# connectors.net
KiCad netlist of a schematic drawn in Altium Designer
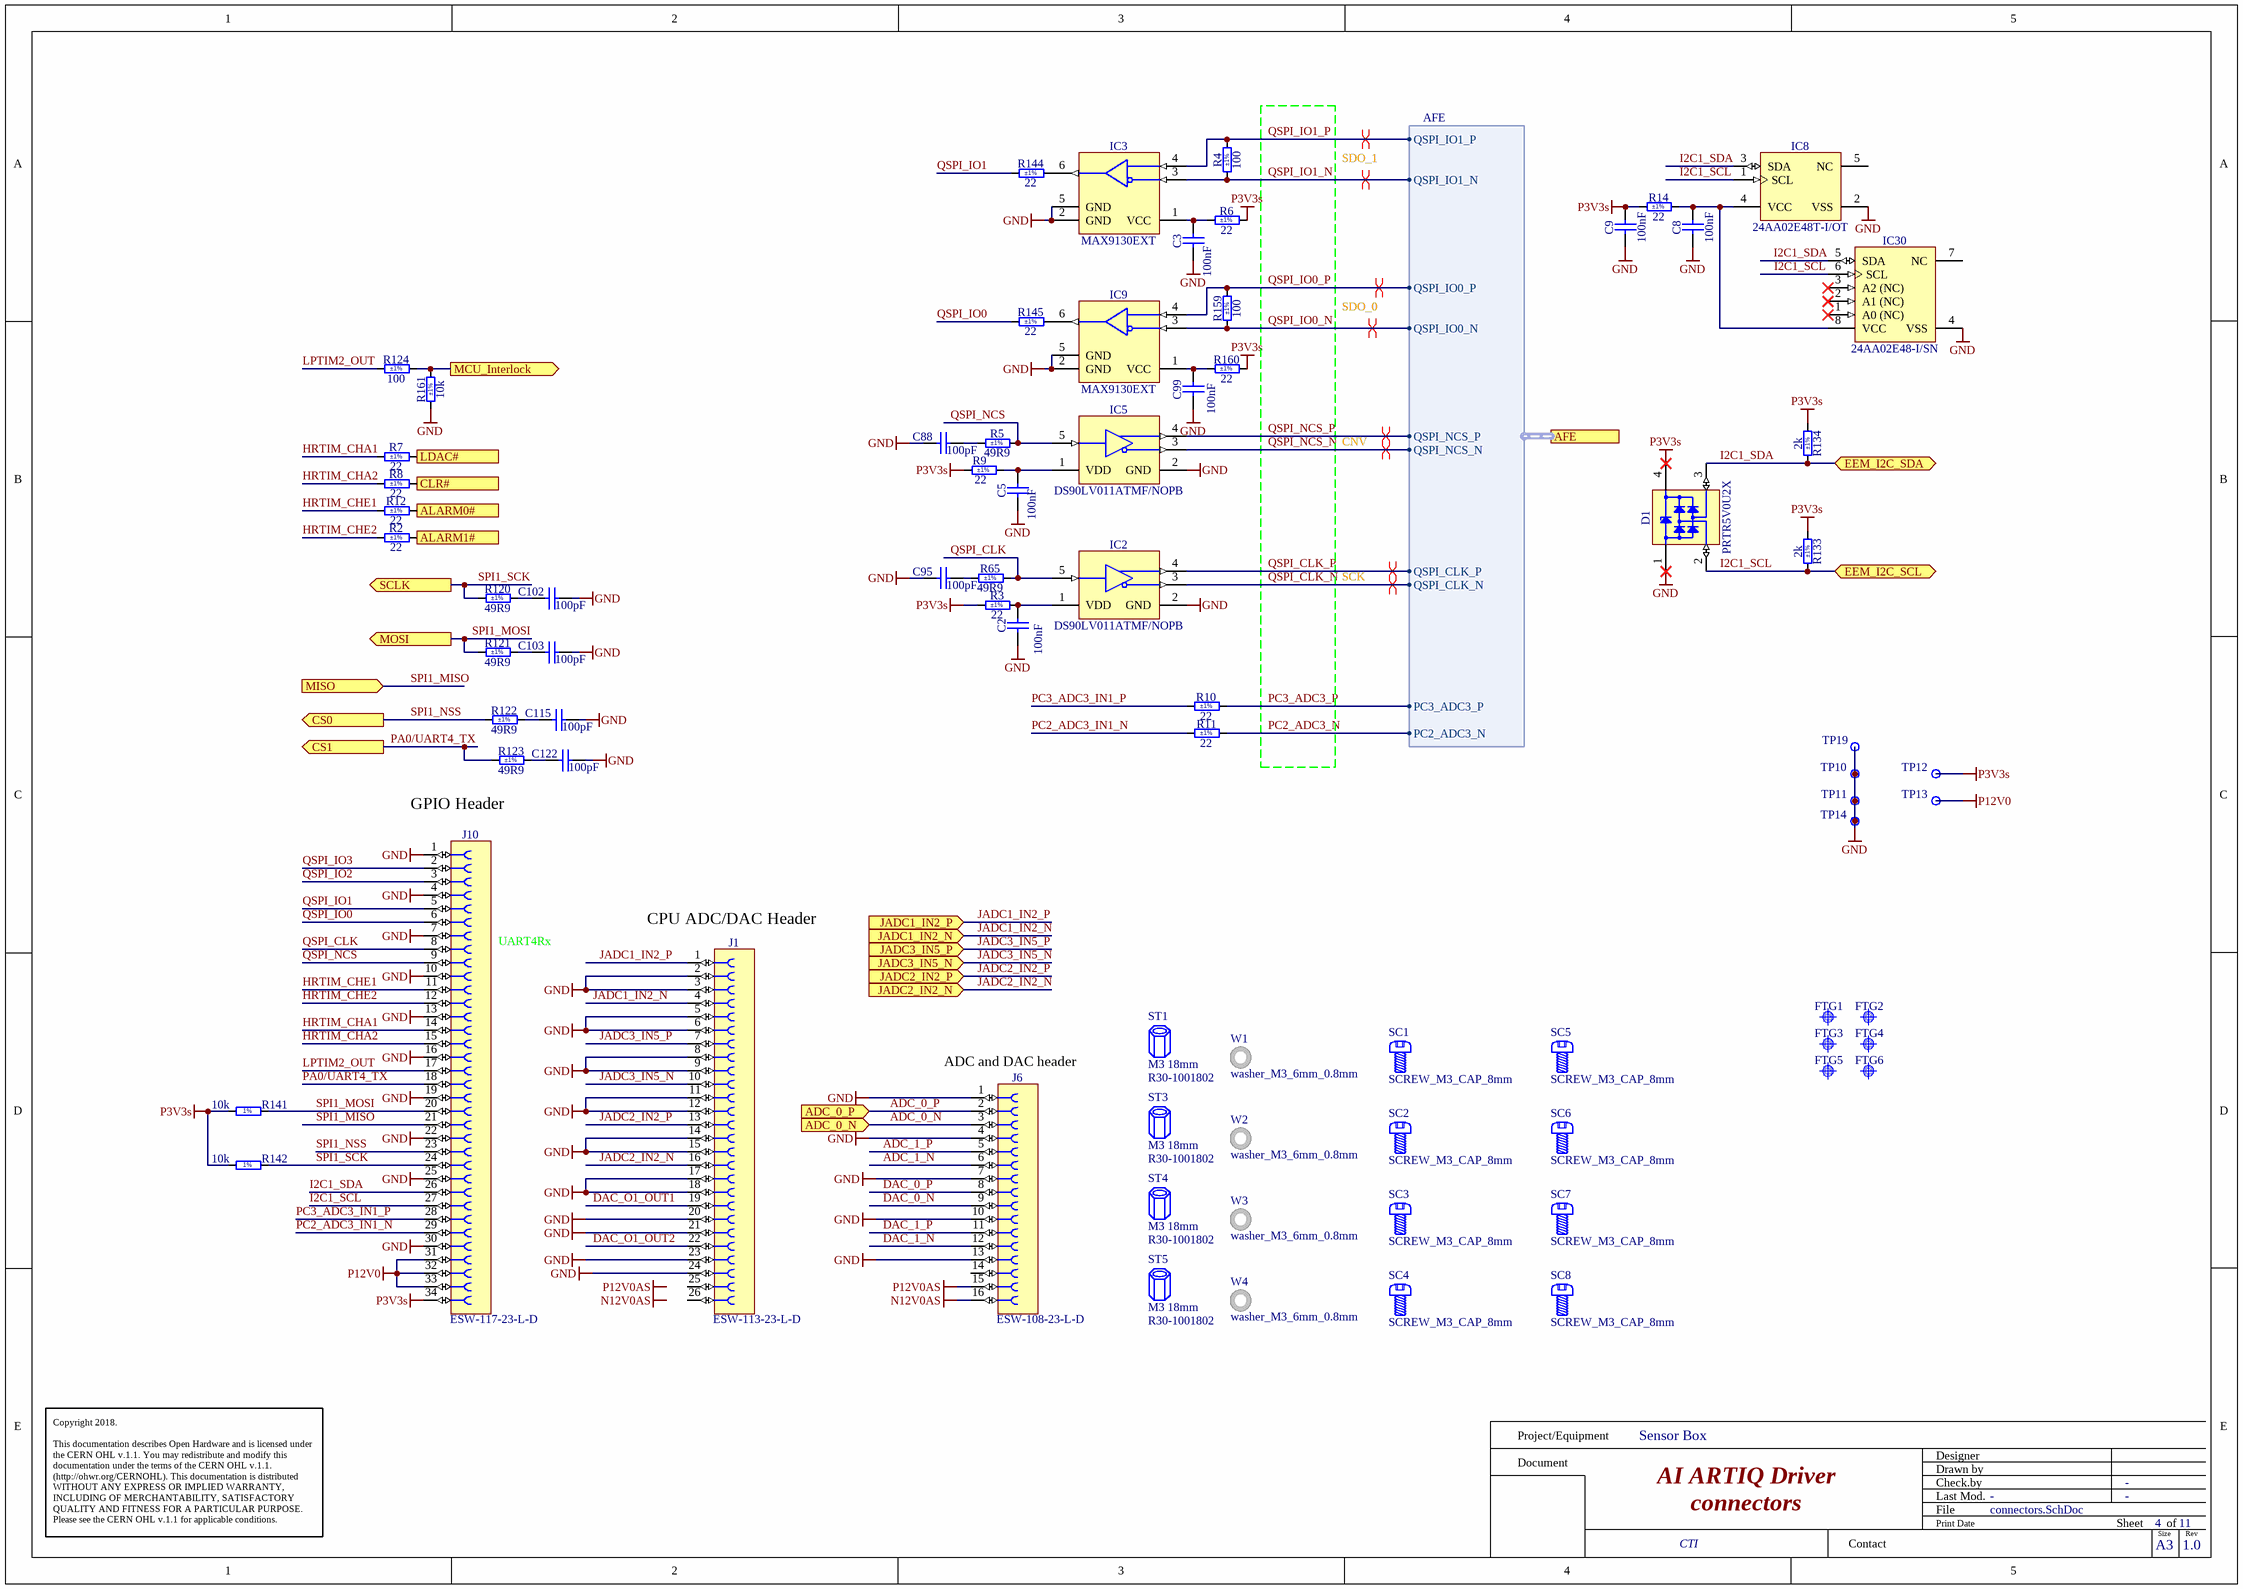
[diagram p0: connectors.SchDoc]

(export (version "E")
  (design (tool "Eeschema 10.0.6"))
  (components
    (comp (ref "C2")
      (value "100nF")
      (footprint "CAPC2012X135N")
      (description "Non-polarised capacitor")
      (fields
        (field (name "PART NUMBER") "CC0805_100NF_50V_10%_X7R")
        (field (name "VOLTAGE") "50V")
        (field (name "AUTHOR") "CERN DEM JLC")
      )
      (libsource (lib "Capacitors") (part "Capacitor - non polarized"))
    )
    (comp (ref "C3")
      (value "100nF")
      (footprint "CAPC2012X135N")
      (description "Non-polarised capacitor")
      (fields
        (field (name "PART NUMBER") "CC0805_100NF_50V_10%_X7R")
        (field (name "VOLTAGE") "50V")
        (field (name "AUTHOR") "CERN DEM JLC")
      )
      (libsource (lib "Capacitors") (part "Capacitor - non polarized"))
    )
    (comp (ref "C5")
      (value "100nF")
      (footprint "CAPC2012X135N")
      (description "Non-polarised capacitor")
      (fields
        (field (name "PART NUMBER") "CC0805_100NF_50V_10%_X7R")
        (field (name "VOLTAGE") "50V")
        (field (name "AUTHOR") "CERN DEM JLC")
      )
      (libsource (lib "Capacitors") (part "Capacitor - non polarized"))
    )
    (comp (ref "C8")
      (value "100nF")
      (footprint "CAPC2012X135N")
      (description "Non-polarised capacitor")
      (fields
        (field (name "PART NUMBER") "CC0805_100NF_50V_10%_X7R")
        (field (name "VOLTAGE") "50V")
        (field (name "AUTHOR") "CERN DEM JLC")
      )
      (libsource (lib "Capacitors") (part "Capacitor - non polarized"))
    )
    (comp (ref "C9")
      (value "100nF")
      (footprint "CAPC2012X135N")
      (description "Non-polarised capacitor")
      (fields
        (field (name "PART NUMBER") "CC0805_100NF_50V_10%_X7R")
        (field (name "VOLTAGE") "50V")
        (field (name "AUTHOR") "CERN DEM JLC")
      )
      (libsource (lib "Capacitors") (part "Capacitor - non polarized"))
    )
    (comp (ref "C88")
      (value "100pF")
      (footprint "CAPC1005X55N")
      (description "Non-polarised capacitor")
      (fields
        (field (name "PART NUMBER") "CC0402_100PF_50V_5%_C0G")
        (field (name "VOLTAGE") "50V")
        (field (name "AUTHOR") "CERN DEM JLC")
      )
      (libsource (lib "Capacitors") (part "Capacitor - non polarized"))
    )
    (comp (ref "C95")
      (value "100pF")
      (footprint "CAPC1005X55N")
      (description "Non-polarised capacitor")
      (fields
        (field (name "PART NUMBER") "CC0402_100PF_50V_5%_C0G")
        (field (name "VOLTAGE") "50V")
        (field (name "AUTHOR") "CERN DEM JLC")
      )
      (libsource (lib "Capacitors") (part "Capacitor - non polarized"))
    )
    (comp (ref "C99")
      (value "100nF")
      (footprint "CAPC2012X135N")
      (description "Non-polarised capacitor")
      (fields
        (field (name "PART NUMBER") "CC0805_100NF_50V_10%_X7R")
        (field (name "VOLTAGE") "50V")
        (field (name "AUTHOR") "CERN DEM JLC")
      )
      (libsource (lib "Capacitors") (part "Capacitor - non polarized"))
    )
    (comp (ref "C102")
      (value "100pF")
      (footprint "CAPC1005X55N")
      (description "Non-polarised capacitor")
      (fields
        (field (name "PART NUMBER") "CC0402_100PF_50V_5%_C0G")
        (field (name "VOLTAGE") "50V")
        (field (name "AUTHOR") "CERN DEM JLC")
      )
      (libsource (lib "Capacitors") (part "Capacitor - non polarized"))
    )
    (comp (ref "C103")
      (value "100pF")
      (footprint "CAPC1005X55N")
      (description "Non-polarised capacitor")
      (fields
        (field (name "PART NUMBER") "CC0402_100PF_50V_5%_C0G")
        (field (name "VOLTAGE") "50V")
        (field (name "AUTHOR") "CERN DEM JLC")
      )
      (libsource (lib "Capacitors") (part "Capacitor - non polarized"))
    )
    (comp (ref "C115")
      (value "100pF")
      (footprint "CAPC1005X55N")
      (description "Non-polarised capacitor")
      (fields
        (field (name "PART NUMBER") "CC0402_100PF_50V_5%_C0G")
        (field (name "VOLTAGE") "50V")
        (field (name "AUTHOR") "CERN DEM JLC")
      )
      (libsource (lib "Capacitors") (part "Capacitor - non polarized"))
    )
    (comp (ref "C122")
      (value "100pF")
      (footprint "CAPC1005X55N")
      (description "Non-polarised capacitor")
      (fields
        (field (name "PART NUMBER") "CC0402_100PF_50V_5%_C0G")
        (field (name "VOLTAGE") "50V")
        (field (name "AUTHOR") "CERN DEM JLC")
      )
      (libsource (lib "Capacitors") (part "Capacitor - non polarized"))
    )
    (comp (ref "D1")
      (value "PRTR5V0U2X")
      (footprint "SOT190P230X110-4N")
      (description "Ultra Low Capacitance Double Rail-to-Rail ESD Protection Diode")
      (fields
        (field (name "VOLTAGE") "5.5V")
        (field (name "MANUFACTURER") "NXP SEMICONDUCTORS")
        (field (name "AUTHOR") "CERN DEM JLC")
      )
      (libsource (lib "ICs And Semiconductors") (part "PRTR5V0U2X"))
    )
    (comp (ref "FTG1")
      (value "Use only in PCB")
      (footprint "FIDUCIAL_TOP_C100-200")
      (description "Fiducial Target")
      (fields (field (name "PART NUMBER") "FIDUCIAL_TARGET_C100-200") (field (name "AUTHOR") "CERN DEM JLC"))
      (libsource (lib "Eletro-mechanical") (part "Fiducial Target"))
    )
    (comp (ref "FTG2")
      (value "Use only in PCB")
      (footprint "FIDUCIAL_TOP_C100-200")
      (description "Fiducial Target")
      (fields (field (name "PART NUMBER") "FIDUCIAL_TARGET_C100-200") (field (name "AUTHOR") "CERN DEM JLC"))
      (libsource (lib "Eletro-mechanical") (part "Fiducial Target"))
    )
    (comp (ref "FTG3")
      (value "Use only in PCB")
      (footprint "FIDUCIAL_TOP_C100-200")
      (description "Fiducial Target")
      (fields (field (name "PART NUMBER") "FIDUCIAL_TARGET_C100-200") (field (name "AUTHOR") "CERN DEM JLC"))
      (libsource (lib "Eletro-mechanical") (part "Fiducial Target"))
    )
    (comp (ref "FTG4")
      (value "Use only in PCB")
      (footprint "FIDUCIAL_TOP_C100-200")
      (description "Fiducial Target")
      (fields (field (name "PART NUMBER") "FIDUCIAL_TARGET_C100-200") (field (name "AUTHOR") "CERN DEM JLC"))
      (libsource (lib "Eletro-mechanical") (part "Fiducial Target"))
    )
    (comp (ref "FTG5")
      (value "Use only in PCB")
      (footprint "FIDUCIAL_TOP_C100-200")
      (description "Fiducial Target")
      (fields (field (name "PART NUMBER") "FIDUCIAL_TARGET_C100-200") (field (name "AUTHOR") "CERN DEM JLC"))
      (libsource (lib "Eletro-mechanical") (part "Fiducial Target"))
    )
    (comp (ref "FTG6")
      (value "Use only in PCB")
      (footprint "FIDUCIAL_TOP_C100-200")
      (description "Fiducial Target")
      (fields (field (name "PART NUMBER") "FIDUCIAL_TARGET_C100-200") (field (name "AUTHOR") "CERN DEM JLC"))
      (libsource (lib "Eletro-mechanical") (part "Fiducial Target"))
    )
    (comp (ref "IC2")
      (value "DS90LV011ATMF/NOPB")
      (footprint "SOT95P284X122-5N")
      (description "3V LVDS Single High Speed Differential Driver")
      (fields
        (field (name "MANUFACTURER") "NATIONAL SEMICONDUCTOR")
        (field (name "MANUFACTURER PART NUMBER") "DS90LV011ATMF")
        (field (name "AUTHOR") "CERN DEM JLC")
      )
      (libsource (lib "ICs And Semiconductors") (part "DS90LV011A"))
    )
    (comp (ref "IC3")
      (value "MAX9130EXT")
      (footprint "SOT65P210X110-6N")
      (description "Single 500Mbps LVDS Line Receiver")
      (fields (field (name "MANUFACTURER") "MAXIM") (field (name "AUTHOR") "CERN DEM HF"))
      (libsource (lib "ICs And Semiconductors") (part "MAX9130"))
    )
    (comp (ref "IC5")
      (value "DS90LV011ATMF/NOPB")
      (footprint "SOT95P284X122-5N")
      (description "3V LVDS Single High Speed Differential Driver")
      (fields
        (field (name "MANUFACTURER") "NATIONAL SEMICONDUCTOR")
        (field (name "MANUFACTURER PART NUMBER") "DS90LV011ATMF")
        (field (name "AUTHOR") "CERN DEM JLC")
      )
      (libsource (lib "ICs And Semiconductors") (part "DS90LV011A"))
    )
    (comp (ref "IC8")
      (value "24AA02E48T-I/OT")
      (footprint "SOT95P280X145-5N")
      (description "1.7V-5.5V, 2K I2C Serial EEPROM With EUI-48 Node Identity")
      (fields (field (name "MANUFACTURER") "MICROCHIP TECHNOLOGY") (field (name "AUTHOR") "CERN DEM MR"))
      (libsource (lib "ICs And Semiconductors") (part "24AA02E48T-I/OT"))
    )
    (comp (ref "IC9")
      (value "MAX9130EXT")
      (footprint "SOT65P210X110-6N")
      (description "Single 500Mbps LVDS Line Receiver")
      (fields (field (name "MANUFACTURER") "MAXIM") (field (name "AUTHOR") "CERN DEM HF"))
      (libsource (lib "ICs And Semiconductors") (part "MAX9130"))
    )
    (comp (ref "IC30")
      (value "24AA02E48-I/SN")
      (footprint "SOIC127P600X175-8N")
      (description "1.7V-5.5V, 2K I2C™ Serial EEPROMs with EUI-48™ Node Identity")
      (fields (field (name "MANUFACTURER") "MICROCHIP TECHNOLOGY") (field (name "AUTHOR") "CERN DEM MR"))
      (libsource (lib "ICS-logic") (part "MEM_24AA02E48-I/SN"))
    )
    (comp (ref "J1")
      (value "ESW-113-23-L-D")
      (footprint "connectors:ESW-113-23-L-D")
      (description "Connector Elevated Socket 26 POS 2.54mm, 13.59mm height")
      (fields
        (field (name "MANUFACTURER") "Samtec")
        (field (name "MANUFACTURER PART NUMBER") "ESW-113-23-L-D")
      )
      (libsource (lib "connectors") (part "ESW-113-23-L-D"))
    )
    (comp (ref "J6")
      (value "ESW-108-23-L-D")
      (footprint "connectors:ESW-108-23-L-D")
      (description "Connector Elevated Socket 16 POS 2.54mm, 13.59mm height")
      (fields
        (field (name "MANUFACTURER") "Samtec")
        (field (name "MANUFACTURER PART NUMBER") "ESW-108-23-L-D")
      )
      (libsource (lib "connectors") (part "ESW-108-23-L-D"))
    )
    (comp (ref "J10")
      (value "ESW-117-23-L-D")
      (footprint "connectors:ESW-117-23-L-D")
      (description "Connector Elevated Socket 34 POS 2.54mm, 13.59mm height")
      (fields
        (field (name "MANUFACTURER") "Samtec")
        (field (name "MANUFACTURER PART NUMBER") "ESW-117-23-L-D")
      )
      (libsource (lib "connectors") (part "ESW-117-23-L-D"))
    )
    (comp (ref "R2")
      (value "22")
      (footprint "RESC1608X55N")
      (description "Resistor - 1%")
      (fields
        (field (name "TOLERANCE") "±1%")
        (field (name "PART NUMBER") "R0603_22R_1%_0.1W_100PPM")
        (field (name "POWER") "0.1W")
        (field (name "AUTHOR") "CERN DEM JLC")
      )
      (libsource (lib "Resistors") (part "Resistor - 1%"))
    )
    (comp (ref "R3")
      (value "22")
      (footprint "RESC1608X55N")
      (description "Resistor - 1%")
      (fields
        (field (name "TOLERANCE") "±1%")
        (field (name "PART NUMBER") "R0603_22R_1%_0.1W_100PPM")
        (field (name "POWER") "0.1W")
        (field (name "AUTHOR") "CERN DEM JLC")
      )
      (libsource (lib "Resistors") (part "Resistor - 1%"))
    )
    (comp (ref "R4")
      (value "100")
      (footprint "RESC1608X55N")
      (description "Resistor - 1%")
      (fields
        (field (name "TOLERANCE") "±1%")
        (field (name "PART NUMBER") "R0603_100R_1%_0.1W_100PPM")
        (field (name "POWER") "0.1W")
        (field (name "AUTHOR") "CERN DEM JLC")
      )
      (libsource (lib "Resistors") (part "Resistor - 1%"))
    )
    (comp (ref "R5")
      (value "49R9")
      (footprint "RESC1005X40N")
      (description "Resistor - 1%")
      (fields
        (field (name "TOLERANCE") "±1%")
        (field (name "PART NUMBER") "R0402_49R9_1%_0.0625W_100PPM")
        (field (name "POWER") "0.0625W")
        (field (name "AUTHOR") "CERN DEM JLC")
      )
      (libsource (lib "Resistors") (part "Resistor - 1%"))
    )
    (comp (ref "R6")
      (value "22")
      (footprint "RESC1608X55N")
      (description "Resistor - 1%")
      (fields
        (field (name "TOLERANCE") "±1%")
        (field (name "PART NUMBER") "R0603_22R_1%_0.1W_100PPM")
        (field (name "POWER") "0.1W")
        (field (name "AUTHOR") "CERN DEM JLC")
      )
      (libsource (lib "Resistors") (part "Resistor - 1%"))
    )
    (comp (ref "R7")
      (value "22")
      (footprint "RESC1608X55N")
      (description "Resistor - 1%")
      (fields
        (field (name "TOLERANCE") "±1%")
        (field (name "PART NUMBER") "R0603_22R_1%_0.1W_100PPM")
        (field (name "POWER") "0.1W")
        (field (name "AUTHOR") "CERN DEM JLC")
      )
      (libsource (lib "Resistors") (part "Resistor - 1%"))
    )
    (comp (ref "R8")
      (value "22")
      (footprint "RESC1608X55N")
      (description "Resistor - 1%")
      (fields
        (field (name "TOLERANCE") "±1%")
        (field (name "PART NUMBER") "R0603_22R_1%_0.1W_100PPM")
        (field (name "POWER") "0.1W")
        (field (name "AUTHOR") "CERN DEM JLC")
      )
      (libsource (lib "Resistors") (part "Resistor - 1%"))
    )
    (comp (ref "R9")
      (value "22")
      (footprint "RESC1608X55N")
      (description "Resistor - 1%")
      (fields
        (field (name "TOLERANCE") "±1%")
        (field (name "PART NUMBER") "R0603_22R_1%_0.1W_100PPM")
        (field (name "POWER") "0.1W")
        (field (name "AUTHOR") "CERN DEM JLC")
      )
      (libsource (lib "Resistors") (part "Resistor - 1%"))
    )
    (comp (ref "R10")
      (value "22")
      (footprint "RESC1608X55N")
      (description "Resistor - 1%")
      (fields
        (field (name "TOLERANCE") "±1%")
        (field (name "PART NUMBER") "R0603_22R_1%_0.1W_100PPM")
        (field (name "POWER") "0.1W")
        (field (name "AUTHOR") "CERN DEM JLC")
      )
      (libsource (lib "Resistors") (part "Resistor - 1%"))
    )
    (comp (ref "R11")
      (value "22")
      (footprint "RESC1608X55N")
      (description "Resistor - 1%")
      (fields
        (field (name "TOLERANCE") "±1%")
        (field (name "PART NUMBER") "R0603_22R_1%_0.1W_100PPM")
        (field (name "POWER") "0.1W")
        (field (name "AUTHOR") "CERN DEM JLC")
      )
      (libsource (lib "Resistors") (part "Resistor - 1%"))
    )
    (comp (ref "R12")
      (value "22")
      (footprint "RESC1608X55N")
      (description "Resistor - 1%")
      (fields
        (field (name "TOLERANCE") "±1%")
        (field (name "PART NUMBER") "R0603_22R_1%_0.1W_100PPM")
        (field (name "POWER") "0.1W")
        (field (name "AUTHOR") "CERN DEM JLC")
      )
      (libsource (lib "Resistors") (part "Resistor - 1%"))
    )
    (comp (ref "R14")
      (value "22")
      (footprint "RESC1608X55N")
      (description "Resistor - 1%")
      (fields
        (field (name "TOLERANCE") "±1%")
        (field (name "PART NUMBER") "R0603_22R_1%_0.1W_100PPM")
        (field (name "POWER") "0.1W")
        (field (name "AUTHOR") "CERN DEM JLC")
      )
      (libsource (lib "Resistors") (part "Resistor - 1%"))
    )
    (comp (ref "R65")
      (value "49R9")
      (footprint "RESC1005X40N")
      (description "Resistor - 1%")
      (fields
        (field (name "TOLERANCE") "±1%")
        (field (name "PART NUMBER") "R0402_49R9_1%_0.0625W_100PPM")
        (field (name "POWER") "0.0625W")
        (field (name "AUTHOR") "CERN DEM JLC")
      )
      (libsource (lib "Resistors") (part "Resistor - 1%"))
    )
    (comp (ref "R120")
      (value "49R9")
      (footprint "RESC1005X40N")
      (description "Resistor - 1%")
      (fields
        (field (name "TOLERANCE") "±1%")
        (field (name "PART NUMBER") "R0402_49R9_1%_0.0625W_100PPM")
        (field (name "POWER") "0.0625W")
        (field (name "AUTHOR") "CERN DEM JLC")
      )
      (libsource (lib "Resistors") (part "Resistor - 1%"))
    )
    (comp (ref "R121")
      (value "49R9")
      (footprint "RESC1005X40N")
      (description "Resistor - 1%")
      (fields
        (field (name "TOLERANCE") "±1%")
        (field (name "PART NUMBER") "R0402_49R9_1%_0.0625W_100PPM")
        (field (name "POWER") "0.0625W")
        (field (name "AUTHOR") "CERN DEM JLC")
      )
      (libsource (lib "Resistors") (part "Resistor - 1%"))
    )
    (comp (ref "R122")
      (value "49R9")
      (footprint "RESC1005X40N")
      (description "Resistor - 1%")
      (fields
        (field (name "TOLERANCE") "±1%")
        (field (name "PART NUMBER") "R0402_49R9_1%_0.0625W_100PPM")
        (field (name "POWER") "0.0625W")
        (field (name "AUTHOR") "CERN DEM JLC")
      )
      (libsource (lib "Resistors") (part "Resistor - 1%"))
    )
    (comp (ref "R123")
      (value "49R9")
      (footprint "RESC1005X40N")
      (description "Resistor - 1%")
      (fields
        (field (name "TOLERANCE") "±1%")
        (field (name "PART NUMBER") "R0402_49R9_1%_0.0625W_100PPM")
        (field (name "POWER") "0.0625W")
        (field (name "AUTHOR") "CERN DEM JLC")
      )
      (libsource (lib "Resistors") (part "Resistor - 1%"))
    )
    (comp (ref "R124")
      (value "100")
      (footprint "RESC1005X40N")
      (description "Resistor - 1%")
      (fields
        (field (name "TOLERANCE") "±1%")
        (field (name "PART NUMBER") "R0402_100R_1%_0.0625W_100PPM")
        (field (name "POWER") "0.0625W")
        (field (name "AUTHOR") "CERN DEM JLC")
      )
      (libsource (lib "Resistors") (part "Resistor - 1%"))
    )
    (comp (ref "R133")
      (value "2k")
      (footprint "RESC1608X55N")
      (description "Resistor - 1%")
      (fields
        (field (name "TOLERANCE") "±1%")
        (field (name "PART NUMBER") "R0603_2K_1%_0.1W_100PPM")
        (field (name "POWER") "0.1W")
        (field (name "AUTHOR") "CERN DEM JLC")
      )
      (libsource (lib "Resistors") (part "Resistor - 1%"))
    )
    (comp (ref "R134")
      (value "2k")
      (footprint "RESC1608X55N")
      (description "Resistor - 1%")
      (fields
        (field (name "TOLERANCE") "±1%")
        (field (name "PART NUMBER") "R0603_2K_1%_0.1W_100PPM")
        (field (name "POWER") "0.1W")
        (field (name "AUTHOR") "CERN DEM JLC")
      )
      (libsource (lib "Resistors") (part "Resistor - 1%"))
    )
    (comp (ref "R141")
      (value "10k")
      (footprint "RESC1005X40N")
      (description "Resistor - 1%")
      (fields
        (field (name "PART NUMBER") "R0402_10K_1%_0.0625W_100PPM")
        (field (name "POWER") "0.0625W")
        (field (name "AUTHOR") "CERN DEM JLC")
      )
      (libsource (lib "") (part "Resistor - 1%_1"))
    )
    (comp (ref "R142")
      (value "10k")
      (footprint "RESC1005X40N")
      (description "Resistor - 1%")
      (fields
        (field (name "PART NUMBER") "R0402_10K_1%_0.0625W_100PPM")
        (field (name "POWER") "0.0625W")
        (field (name "AUTHOR") "CERN DEM JLC")
      )
      (libsource (lib "") (part "Resistor - 1%_1"))
    )
    (comp (ref "R144")
      (value "22")
      (footprint "RESC1608X55N")
      (description "Resistor - 1%")
      (fields
        (field (name "TOLERANCE") "±1%")
        (field (name "PART NUMBER") "R0603_22R_1%_0.1W_100PPM")
        (field (name "POWER") "0.1W")
        (field (name "AUTHOR") "CERN DEM JLC")
      )
      (libsource (lib "Resistors") (part "Resistor - 1%"))
    )
    (comp (ref "R145")
      (value "22")
      (footprint "RESC1608X55N")
      (description "Resistor - 1%")
      (fields
        (field (name "TOLERANCE") "±1%")
        (field (name "PART NUMBER") "R0603_22R_1%_0.1W_100PPM")
        (field (name "POWER") "0.1W")
        (field (name "AUTHOR") "CERN DEM JLC")
      )
      (libsource (lib "Resistors") (part "Resistor - 1%"))
    )
    (comp (ref "R159")
      (value "100")
      (footprint "RESC1608X55N")
      (description "Resistor - 1%")
      (fields
        (field (name "TOLERANCE") "±1%")
        (field (name "PART NUMBER") "R0603_100R_1%_0.1W_100PPM")
        (field (name "POWER") "0.1W")
        (field (name "AUTHOR") "CERN DEM JLC")
      )
      (libsource (lib "Resistors") (part "Resistor - 1%"))
    )
    (comp (ref "R160")
      (value "22")
      (footprint "RESC1608X55N")
      (description "Resistor - 1%")
      (fields
        (field (name "TOLERANCE") "±1%")
        (field (name "PART NUMBER") "R0603_22R_1%_0.1W_100PPM")
        (field (name "POWER") "0.1W")
        (field (name "AUTHOR") "CERN DEM JLC")
      )
      (libsource (lib "Resistors") (part "Resistor - 1%"))
    )
    (comp (ref "R161")
      (value "10k")
      (footprint "RESC1005X40N")
      (description "Resistor - 1%")
      (fields
        (field (name "TOLERANCE") "±1%")
        (field (name "PART NUMBER") "R0402_10K_1%_0.0625W_100PPM")
        (field (name "POWER") "0.0625W")
        (field (name "AUTHOR") "CERN DEM JLC")
      )
      (libsource (lib "Resistors") (part "Resistor - 1%"))
    )
    (comp (ref "SC1")
      (value "SCREW_M3_CAP_8mm")
      (footprint "mechanical:SCREW_M3_CAP_8mm")
      (description "M3 x 8mm cap head screw")
      (fields
        (field (name "MANUFACTURER") "Accu Limited")
        (field (name "MANUFACTURER PART NUMBER") "SSCF-M3-8-12.9-Z")
      )
      (libsource (lib "mechanical") (part "SCREW_M3_CAP_8mm"))
    )
    (comp (ref "SC2")
      (value "SCREW_M3_CAP_8mm")
      (footprint "mechanical:SCREW_M3_CAP_8mm")
      (description "M3 x 8mm cap head screw")
      (fields
        (field (name "MANUFACTURER") "Accu Limited")
        (field (name "MANUFACTURER PART NUMBER") "SSCF-M3-8-12.9-Z")
      )
      (libsource (lib "mechanical") (part "SCREW_M3_CAP_8mm"))
    )
    (comp (ref "SC3")
      (value "SCREW_M3_CAP_8mm")
      (footprint "mechanical:SCREW_M3_CAP_8mm")
      (description "M3 x 8mm cap head screw")
      (fields
        (field (name "MANUFACTURER") "Accu Limited")
        (field (name "MANUFACTURER PART NUMBER") "SSCF-M3-8-12.9-Z")
      )
      (libsource (lib "mechanical") (part "SCREW_M3_CAP_8mm"))
    )
    (comp (ref "SC4")
      (value "SCREW_M3_CAP_8mm")
      (footprint "mechanical:SCREW_M3_CAP_8mm")
      (description "M3 x 8mm cap head screw")
      (fields
        (field (name "MANUFACTURER") "Accu Limited")
        (field (name "MANUFACTURER PART NUMBER") "SSCF-M3-8-12.9-Z")
      )
      (libsource (lib "mechanical") (part "SCREW_M3_CAP_8mm"))
    )
    (comp (ref "SC5")
      (value "SCREW_M3_CAP_8mm")
      (footprint "mechanical:SCREW_M3_CAP_8mm")
      (description "M3 x 8mm cap head screw")
      (fields
        (field (name "MANUFACTURER") "Accu Limited")
        (field (name "MANUFACTURER PART NUMBER") "SSCF-M3-8-12.9-Z")
      )
      (libsource (lib "mechanical") (part "SCREW_M3_CAP_8mm"))
    )
    (comp (ref "SC6")
      (value "SCREW_M3_CAP_8mm")
      (footprint "mechanical:SCREW_M3_CAP_8mm")
      (description "M3 x 8mm cap head screw")
      (fields
        (field (name "MANUFACTURER") "Accu Limited")
        (field (name "MANUFACTURER PART NUMBER") "SSCF-M3-8-12.9-Z")
      )
      (libsource (lib "mechanical") (part "SCREW_M3_CAP_8mm"))
    )
    (comp (ref "SC7")
      (value "SCREW_M3_CAP_8mm")
      (footprint "mechanical:SCREW_M3_CAP_8mm")
      (description "M3 x 8mm cap head screw")
      (fields
        (field (name "MANUFACTURER") "Accu Limited")
        (field (name "MANUFACTURER PART NUMBER") "SSCF-M3-8-12.9-Z")
      )
      (libsource (lib "mechanical") (part "SCREW_M3_CAP_8mm"))
    )
    (comp (ref "SC8")
      (value "SCREW_M3_CAP_8mm")
      (footprint "mechanical:SCREW_M3_CAP_8mm")
      (description "M3 x 8mm cap head screw")
      (fields
        (field (name "MANUFACTURER") "Accu Limited")
        (field (name "MANUFACTURER PART NUMBER") "SSCF-M3-8-12.9-Z")
      )
      (libsource (lib "mechanical") (part "SCREW_M3_CAP_8mm"))
    )
    (comp (ref "ST1")
      (value "M3 18mm")
      (footprint "mechanical:R30-1001802")
      (description "M3.0x18 standoff")
      (fields (field (name "MANUFACTURER") "Harwin") (field (name "MANUFACTURER PART NUMBER") "R30-1001802"))
      (libsource (lib "mechanical") (part "STANDOFF_HARWIN_R30_1001802"))
    )
    (comp (ref "ST3")
      (value "M3 18mm")
      (footprint "mechanical:R30-1001802")
      (description "M3.0x18 standoff")
      (fields (field (name "MANUFACTURER") "Harwin") (field (name "MANUFACTURER PART NUMBER") "R30-1001802"))
      (libsource (lib "mechanical") (part "STANDOFF_HARWIN_R30_1001802"))
    )
    (comp (ref "ST4")
      (value "M3 18mm")
      (footprint "mechanical:R30-1001802")
      (description "M3.0x18 standoff")
      (fields (field (name "MANUFACTURER") "Harwin") (field (name "MANUFACTURER PART NUMBER") "R30-1001802"))
      (libsource (lib "mechanical") (part "STANDOFF_HARWIN_R30_1001802"))
    )
    (comp (ref "ST5")
      (value "M3 18mm")
      (footprint "mechanical:R30-1001802")
      (description "M3.0x18 standoff")
      (fields (field (name "MANUFACTURER") "Harwin") (field (name "MANUFACTURER PART NUMBER") "R30-1001802"))
      (libsource (lib "mechanical") (part "STANDOFF_HARWIN_R30_1001802"))
    )
    (comp (ref "TP10")
      (value "Test Point")
      (footprint "TPS127")
      (fields (field (name "PART NUMBER") "SMD_PAD_1.27X1.27MM") (field (name "AUTHOR") "CERN DEM JLC"))
      (libsource (lib "Eletro-mechanical") (part "Test Point"))
    )
    (comp (ref "TP11")
      (value "Test Point")
      (footprint "TPS127")
      (fields (field (name "PART NUMBER") "SMD_PAD_1.27X1.27MM") (field (name "AUTHOR") "CERN DEM JLC"))
      (libsource (lib "Eletro-mechanical") (part "Test Point"))
    )
    (comp (ref "TP12")
      (value "Test Point")
      (footprint "TPS127")
      (fields (field (name "PART NUMBER") "SMD_PAD_1.27X1.27MM") (field (name "AUTHOR") "CERN DEM JLC"))
      (libsource (lib "Eletro-mechanical") (part "Test Point"))
    )
    (comp (ref "TP13")
      (value "Test Point")
      (footprint "TPS127")
      (fields (field (name "PART NUMBER") "SMD_PAD_1.27X1.27MM") (field (name "AUTHOR") "CERN DEM JLC"))
      (libsource (lib "Eletro-mechanical") (part "Test Point"))
    )
    (comp (ref "TP14")
      (value "Test Point")
      (footprint "TPS127")
      (fields (field (name "PART NUMBER") "SMD_PAD_1.27X1.27MM") (field (name "AUTHOR") "CERN DEM JLC"))
      (libsource (lib "Eletro-mechanical") (part "Test Point"))
    )
    (comp (ref "TP19")
      (value "Test Point")
      (footprint "VERO_20-313145")
      (fields
        (field (name "PART NUMBER") "VERO_20-313145")
        (field (name "MANUFACTURER") "VERO TECHNOLOGIES")
        (field (name "MANUFACTURER PART NUMBER") "20-313145")
        (field (name "AUTHOR") "CERN DEM JLC")
      )
      (libsource (lib "Connectors") (part "Test Point"))
    )
    (comp (ref "W1")
      (value "washer_M3_6mm_0.8mm")
      (footprint "mechanical:washer_M3_6mm_0.8mm")
      (description "M3 Washer:\r\nID: 3.2mm\r\nOD: 6mm\r\nThickness 0.8mm")
      (fields
        (field (name "MANUFACTURER") "Accu Limited")
        (field (name "MANUFACTURER PART NUMBER") "HAFZ-M3-A4")
      )
      (libsource (lib "mechanical") (part "washer_M3_6mm_0.8mm"))
    )
    (comp (ref "W2")
      (value "washer_M3_6mm_0.8mm")
      (footprint "mechanical:washer_M3_6mm_0.8mm")
      (description "M3 Washer:\r\nID: 3.2mm\r\nOD: 6mm\r\nThickness 0.8mm")
      (fields
        (field (name "MANUFACTURER") "Accu Limited")
        (field (name "MANUFACTURER PART NUMBER") "HAFZ-M3-A4")
      )
      (libsource (lib "mechanical") (part "washer_M3_6mm_0.8mm"))
    )
    (comp (ref "W3")
      (value "washer_M3_6mm_0.8mm")
      (footprint "mechanical:washer_M3_6mm_0.8mm")
      (description "M3 Washer:\r\nID: 3.2mm\r\nOD: 6mm\r\nThickness 0.8mm")
      (fields
        (field (name "MANUFACTURER") "Accu Limited")
        (field (name "MANUFACTURER PART NUMBER") "HAFZ-M3-A4")
      )
      (libsource (lib "mechanical") (part "washer_M3_6mm_0.8mm"))
    )
    (comp (ref "W4")
      (value "washer_M3_6mm_0.8mm")
      (footprint "mechanical:washer_M3_6mm_0.8mm")
      (description "M3 Washer:\r\nID: 3.2mm\r\nOD: 6mm\r\nThickness 0.8mm")
      (fields
        (field (name "MANUFACTURER") "Accu Limited")
        (field (name "MANUFACTURER PART NUMBER") "HAFZ-M3-A4")
      )
      (libsource (lib "mechanical") (part "washer_M3_6mm_0.8mm"))
    )
  )
  (nets
    (net (code "2") (name "/ADC_0_N") (class "Default")
      (node (ref "J6") (pin "3") (pinfunction "3_3") (pintype "bidirectional"))
    )
    (net (code "3") (name "/ADC_0_P") (class "Default")
      (node (ref "J6") (pin "2") (pinfunction "2_2") (pintype "bidirectional"))
    )
    (net (code "4") (name "/ADC_1_N") (class "Default")
      (node (ref "J6") (pin "6") (pinfunction "6_6") (pintype "bidirectional"))
    )
    (net (code "5") (name "/ADC_1_P") (class "Default")
      (node (ref "J6") (pin "5") (pinfunction "5_5") (pintype "bidirectional"))
    )
    (net (code "6") (name "/ALARM0#") (class "Default")
      (node (ref "R12") (pin "2") (pinfunction "2_2") (pintype "passive"))
    )
    (net (code "7") (name "/ALARM1#") (class "Default")
      (node (ref "R2") (pin "2") (pinfunction "2_2") (pintype "passive"))
    )
    (net (code "8") (name "/CLR#") (class "Default")
      (node (ref "R8") (pin "2") (pinfunction "2_2") (pintype "passive"))
    )
    (net (code "9") (name "/DAC_0_N") (class "Default")
      (node (ref "J6") (pin "9") (pinfunction "9_9") (pintype "bidirectional"))
    )
    (net (code "10") (name "/DAC_0_P") (class "Default")
      (node (ref "J6") (pin "8") (pinfunction "8_8") (pintype "bidirectional"))
    )
    (net (code "11") (name "/DAC_1_N") (class "Default")
      (node (ref "J6") (pin "12") (pinfunction "12_12") (pintype "bidirectional"))
    )
    (net (code "12") (name "/DAC_1_P") (class "Default")
      (node (ref "J6") (pin "11") (pinfunction "11_11") (pintype "bidirectional"))
    )
    (net (code "13") (name "/DAC_O1_OUT1") (class "Default")
      (node (ref "J1") (pin "19") (pinfunction "19_19") (pintype "bidirectional"))
    )
    (net (code "14") (name "/DAC_O1_OUT2") (class "Default")
      (node (ref "J1") (pin "22") (pinfunction "22_22") (pintype "bidirectional"))
    )
    (net (code "15") (name "/HRTIM_CHA1") (class "Default")
      (node (ref "J10") (pin "14") (pinfunction "14_14") (pintype "bidirectional"))
      (node (ref "R7") (pin "1") (pinfunction "1_1") (pintype "passive"))
    )
    (net (code "16") (name "/HRTIM_CHA2") (class "Default")
      (node (ref "J10") (pin "15") (pinfunction "15_15") (pintype "bidirectional"))
      (node (ref "R8") (pin "1") (pinfunction "1_1") (pintype "passive"))
    )
    (net (code "17") (name "/HRTIM_CHE1") (class "Default")
      (node (ref "J10") (pin "11") (pinfunction "11_11") (pintype "bidirectional"))
      (node (ref "R12") (pin "1") (pinfunction "1_1") (pintype "passive"))
    )
    (net (code "18") (name "/HRTIM_CHE2") (class "Default")
      (node (ref "J10") (pin "12") (pinfunction "12_12") (pintype "bidirectional"))
      (node (ref "R2") (pin "1") (pinfunction "1_1") (pintype "passive"))
    )
    (net (code "19") (name "/I2C1_SCL") (class "Default")
      (node (ref "D1") (pin "2") (pinfunction "I/O1_2") (pintype "bidirectional"))
      (node (ref "IC30") (pin "6") (pinfunction "SCL_6") (pintype "input"))
      (node (ref "IC8") (pin "1") (pinfunction "SCL_1") (pintype "input"))
      (node (ref "J10") (pin "27") (pinfunction "27_27") (pintype "bidirectional"))
      (node (ref "R133") (pin "2") (pinfunction "2_2") (pintype "passive"))
    )
    (net (code "20") (name "/I2C1_SDA") (class "Default")
      (node (ref "D1") (pin "3") (pinfunction "I/O2_3") (pintype "bidirectional"))
      (node (ref "IC30") (pin "5") (pinfunction "SDA_5") (pintype "bidirectional"))
      (node (ref "IC8") (pin "3") (pinfunction "SDA_3") (pintype "bidirectional"))
      (node (ref "J10") (pin "26") (pinfunction "26_26") (pintype "bidirectional"))
      (node (ref "R134") (pin "2") (pinfunction "2_2") (pintype "passive"))
    )
    (net (code "21") (name "/JADC1_IN2_N") (class "Default")
      (node (ref "J1") (pin "4") (pinfunction "4_4") (pintype "bidirectional"))
    )
    (net (code "22") (name "/JADC1_IN2_P") (class "Default")
      (node (ref "J1") (pin "1") (pinfunction "1_1") (pintype "bidirectional"))
    )
    (net (code "23") (name "/JADC2_IN2_N") (class "Default")
      (node (ref "J1") (pin "16") (pinfunction "16_16") (pintype "bidirectional"))
    )
    (net (code "24") (name "/JADC2_IN2_P") (class "Default")
      (node (ref "J1") (pin "13") (pinfunction "13_13") (pintype "bidirectional"))
    )
    (net (code "25") (name "/JADC3_IN5_N") (class "Default")
      (node (ref "J1") (pin "10") (pinfunction "10_10") (pintype "bidirectional"))
    )
    (net (code "26") (name "/JADC3_IN5_P") (class "Default")
      (node (ref "J1") (pin "7") (pinfunction "7_7") (pintype "bidirectional"))
    )
    (net (code "27") (name "/LDAC#") (class "Default")
      (node (ref "R7") (pin "2") (pinfunction "2_2") (pintype "passive"))
    )
    (net (code "28") (name "/LPTIM2_OUT") (class "Default")
      (node (ref "J10") (pin "17") (pinfunction "17_17") (pintype "bidirectional"))
      (node (ref "R124") (pin "1") (pinfunction "1_1") (pintype "passive"))
    )
    (net (code "29") (name "/MCU_Interlock") (class "Default")
      (node (ref "R124") (pin "2") (pinfunction "2_2") (pintype "passive"))
      (node (ref "R161") (pin "2") (pinfunction "2_2") (pintype "passive"))
    )
    (net (code "30") (name "/PA0{slash}UART4_TX") (class "Default")
      (node (ref "J10") (pin "18") (pinfunction "18_18") (pintype "bidirectional"))
      (node (ref "R123") (pin "1") (pinfunction "1_1") (pintype "passive"))
    )
    (net (code "31") (name "/PC2_ADC3_IN1_N") (class "Default")
      (node (ref "J10") (pin "29") (pinfunction "29_29") (pintype "bidirectional"))
      (node (ref "R11") (pin "1") (pinfunction "1_1") (pintype "passive"))
    )
    (net (code "32") (name "/PC2_ADC3_N") (class "Default")
      (node (ref "R11") (pin "2") (pinfunction "2_2") (pintype "passive"))
    )
    (net (code "33") (name "/PC3_ADC3_IN1_P") (class "Default")
      (node (ref "J10") (pin "28") (pinfunction "28_28") (pintype "bidirectional"))
      (node (ref "R10") (pin "1") (pinfunction "1_1") (pintype "passive"))
    )
    (net (code "34") (name "/PC3_ADC3_P") (class "Default")
      (node (ref "R10") (pin "2") (pinfunction "2_2") (pintype "passive"))
    )
    (net (code "35") (name "/QSPI_CLK") (class "Default")
      (node (ref "IC2") (pin "5") (pinfunction "TTLIN_5") (pintype "input"))
      (node (ref "J10") (pin "8") (pinfunction "8_8") (pintype "bidirectional"))
      (node (ref "R65") (pin "2") (pinfunction "2_2") (pintype "passive"))
    )
    (net (code "36") (name "/QSPI_CLK_N") (class "Default")
      (node (ref "IC2") (pin "3") (pinfunction "OUT-_3") (pintype "output"))
    )
    (net (code "37") (name "/QSPI_CLK_P") (class "Default")
      (node (ref "IC2") (pin "4") (pinfunction "OUT+_4") (pintype "output"))
    )
    (net (code "38") (name "/QSPI_IO0") (class "Default")
      (node (ref "J10") (pin "6") (pinfunction "6_6") (pintype "bidirectional"))
      (node (ref "R145") (pin "1") (pinfunction "1_1") (pintype "passive"))
    )
    (net (code "39") (name "/QSPI_IO0_N") (class "Default")
      (node (ref "IC9") (pin "3") (pinfunction "IN-_3") (pintype "input"))
      (node (ref "R159") (pin "1") (pinfunction "1_1") (pintype "passive"))
    )
    (net (code "40") (name "/QSPI_IO0_P") (class "Default")
      (node (ref "IC9") (pin "4") (pinfunction "IN+_4") (pintype "input"))
      (node (ref "R159") (pin "2") (pinfunction "2_2") (pintype "passive"))
    )
    (net (code "41") (name "/QSPI_IO1") (class "Default")
      (node (ref "J10") (pin "5") (pinfunction "5_5") (pintype "bidirectional"))
      (node (ref "R144") (pin "1") (pinfunction "1_1") (pintype "passive"))
    )
    (net (code "42") (name "/QSPI_IO1_N") (class "Default")
      (node (ref "IC3") (pin "3") (pinfunction "IN-_3") (pintype "input"))
      (node (ref "R4") (pin "1") (pinfunction "1_1") (pintype "passive"))
    )
    (net (code "43") (name "/QSPI_IO1_P") (class "Default")
      (node (ref "IC3") (pin "4") (pinfunction "IN+_4") (pintype "input"))
      (node (ref "R4") (pin "2") (pinfunction "2_2") (pintype "passive"))
    )
    (net (code "44") (name "/QSPI_IO2") (class "Default")
      (node (ref "J10") (pin "3") (pinfunction "3_3") (pintype "bidirectional"))
    )
    (net (code "45") (name "/QSPI_IO3") (class "Default")
      (node (ref "J10") (pin "2") (pinfunction "2_2") (pintype "bidirectional"))
    )
    (net (code "46") (name "/QSPI_NCS") (class "Default")
      (node (ref "IC5") (pin "5") (pinfunction "TTLIN_5") (pintype "input"))
      (node (ref "J10") (pin "9") (pinfunction "9_9") (pintype "bidirectional"))
      (node (ref "R5") (pin "2") (pinfunction "2_2") (pintype "passive"))
    )
    (net (code "47") (name "/QSPI_NCS_N") (class "Default")
      (node (ref "IC5") (pin "3") (pinfunction "OUT-_3") (pintype "output"))
    )
    (net (code "48") (name "/QSPI_NCS_P") (class "Default")
      (node (ref "IC5") (pin "4") (pinfunction "OUT+_4") (pintype "output"))
    )
    (net (code "49") (name "/SPI1_MISO") (class "Default")
      (node (ref "J10") (pin "21") (pinfunction "21_21") (pintype "bidirectional"))
    )
    (net (code "50") (name "/SPI1_MOSI") (class "Default")
      (node (ref "J10") (pin "20") (pinfunction "20_20") (pintype "bidirectional"))
      (node (ref "R121") (pin "1") (pinfunction "1_1") (pintype "passive"))
      (node (ref "R141") (pin "2") (pinfunction "2_2") (pintype "passive"))
    )
    (net (code "51") (name "/SPI1_NSS") (class "Default")
      (node (ref "J10") (pin "23") (pinfunction "23_23") (pintype "bidirectional"))
      (node (ref "R122") (pin "1") (pinfunction "1_1") (pintype "passive"))
    )
    (net (code "52") (name "/SPI1_SCK") (class "Default")
      (node (ref "J10") (pin "24") (pinfunction "24_24") (pintype "bidirectional"))
      (node (ref "R120") (pin "1") (pinfunction "1_1") (pintype "passive"))
      (node (ref "R142") (pin "2") (pinfunction "2_2") (pintype "passive"))
    )
    (net (code "54") (name "GND") (class "Default")
      (node (ref "C102") (pin "2") (pinfunction "2_2") (pintype "passive"))
      (node (ref "C103") (pin "2") (pinfunction "2_2") (pintype "passive"))
      (node (ref "C115") (pin "2") (pinfunction "2_2") (pintype "passive"))
      (node (ref "C122") (pin "2") (pinfunction "2_2") (pintype "passive"))
      (node (ref "C2") (pin "1") (pinfunction "1_1") (pintype "passive"))
      (node (ref "C3") (pin "1") (pinfunction "1_1") (pintype "passive"))
      (node (ref "C5") (pin "1") (pinfunction "1_1") (pintype "passive"))
      (node (ref "C8") (pin "1") (pinfunction "1_1") (pintype "passive"))
      (node (ref "C88") (pin "1") (pinfunction "1_1") (pintype "passive"))
      (node (ref "C9") (pin "1") (pinfunction "1_1") (pintype "passive"))
      (node (ref "C95") (pin "1") (pinfunction "1_1") (pintype "passive"))
      (node (ref "C99") (pin "1") (pinfunction "1_1") (pintype "passive"))
      (node (ref "D1") (pin "1") (pinfunction "GND_1") (pintype "power_in"))
      (node (ref "IC2") (pin "2") (pinfunction "GND_2") (pintype "power_in"))
      (node (ref "IC3") (pin "2") (pinfunction "GND_2") (pintype "power_in"))
      (node (ref "IC3") (pin "5") (pinfunction "GND_5") (pintype "power_in"))
      (node (ref "IC30") (pin "4") (pinfunction "VSS_4") (pintype "power_in"))
      (node (ref "IC5") (pin "2") (pinfunction "GND_2") (pintype "power_in"))
      (node (ref "IC8") (pin "2") (pinfunction "VSS_2") (pintype "power_in"))
      (node (ref "IC9") (pin "2") (pinfunction "GND_2") (pintype "power_in"))
      (node (ref "IC9") (pin "5") (pinfunction "GND_5") (pintype "power_in"))
      (node (ref "J1") (pin "11") (pinfunction "11_11") (pintype "bidirectional"))
      (node (ref "J1") (pin "12") (pinfunction "12_12") (pintype "bidirectional"))
      (node (ref "J1") (pin "14") (pinfunction "14_14") (pintype "bidirectional"))
      (node (ref "J1") (pin "15") (pinfunction "15_15") (pintype "bidirectional"))
      (node (ref "J1") (pin "17") (pinfunction "17_17") (pintype "bidirectional"))
      (node (ref "J1") (pin "18") (pinfunction "18_18") (pintype "bidirectional"))
      (node (ref "J1") (pin "2") (pinfunction "2_2") (pintype "bidirectional"))
      (node (ref "J1") (pin "20") (pinfunction "20_20") (pintype "bidirectional"))
      (node (ref "J1") (pin "21") (pinfunction "21_21") (pintype "bidirectional"))
      (node (ref "J1") (pin "23") (pinfunction "23_23") (pintype "bidirectional"))
      (node (ref "J1") (pin "24") (pinfunction "24_24") (pintype "bidirectional"))
      (node (ref "J1") (pin "3") (pinfunction "3_3") (pintype "bidirectional"))
      (node (ref "J1") (pin "5") (pinfunction "5_5") (pintype "bidirectional"))
      (node (ref "J1") (pin "6") (pinfunction "6_6") (pintype "bidirectional"))
      (node (ref "J1") (pin "8") (pinfunction "8_8") (pintype "bidirectional"))
      (node (ref "J1") (pin "9") (pinfunction "9_9") (pintype "bidirectional"))
      (node (ref "J10") (pin "1") (pinfunction "1_1") (pintype "bidirectional"))
      (node (ref "J10") (pin "10") (pinfunction "10_10") (pintype "bidirectional"))
      (node (ref "J10") (pin "13") (pinfunction "13_13") (pintype "bidirectional"))
      (node (ref "J10") (pin "16") (pinfunction "16_16") (pintype "bidirectional"))
      (node (ref "J10") (pin "19") (pinfunction "19_19") (pintype "bidirectional"))
      (node (ref "J10") (pin "22") (pinfunction "22_22") (pintype "bidirectional"))
      (node (ref "J10") (pin "25") (pinfunction "25_25") (pintype "bidirectional"))
      (node (ref "J10") (pin "30") (pinfunction "30_30") (pintype "bidirectional"))
      (node (ref "J10") (pin "4") (pinfunction "4_4") (pintype "bidirectional"))
      (node (ref "J10") (pin "7") (pinfunction "7_7") (pintype "bidirectional"))
      (node (ref "J6") (pin "1") (pinfunction "1_1") (pintype "bidirectional"))
      (node (ref "J6") (pin "10") (pinfunction "10_10") (pintype "bidirectional"))
      (node (ref "J6") (pin "13") (pinfunction "13_13") (pintype "bidirectional"))
      (node (ref "J6") (pin "4") (pinfunction "4_4") (pintype "bidirectional"))
      (node (ref "J6") (pin "7") (pinfunction "7_7") (pintype "bidirectional"))
      (node (ref "R161") (pin "1") (pinfunction "1_1") (pintype "passive"))
      (node (ref "TP10") (pin "1") (pinfunction "1_1") (pintype "bidirectional"))
      (node (ref "TP11") (pin "1") (pinfunction "1_1") (pintype "bidirectional"))
      (node (ref "TP14") (pin "1") (pinfunction "1_1") (pintype "bidirectional"))
      (node (ref "TP19") (pin "1") (pinfunction "1_1") (pintype "bidirectional"))
    )
    (net (code "55") (name "N12V0AS") (class "Default")
      (node (ref "J6") (pin "16") (pinfunction "16_16") (pintype "bidirectional"))
    )
    (net (code "56") (name "Net-(C88-Pad2)") (class "Default")
      (node (ref "C88") (pin "2") (pinfunction "2_2") (pintype "passive"))
      (node (ref "R5") (pin "1") (pinfunction "1_1") (pintype "passive"))
    )
    (net (code "57") (name "Net-(C95-Pad2)") (class "Default")
      (node (ref "C95") (pin "2") (pinfunction "2_2") (pintype "passive"))
      (node (ref "R65") (pin "1") (pinfunction "1_1") (pintype "passive"))
    )
    (net (code "58") (name "Net-(C102-Pad1)") (class "Default")
      (node (ref "C102") (pin "1") (pinfunction "1_1") (pintype "passive"))
      (node (ref "R120") (pin "2") (pinfunction "2_2") (pintype "passive"))
    )
    (net (code "59") (name "Net-(C103-Pad1)") (class "Default")
      (node (ref "C103") (pin "1") (pinfunction "1_1") (pintype "passive"))
      (node (ref "R121") (pin "2") (pinfunction "2_2") (pintype "passive"))
    )
    (net (code "60") (name "Net-(C115-Pad1)") (class "Default")
      (node (ref "C115") (pin "1") (pinfunction "1_1") (pintype "passive"))
      (node (ref "R122") (pin "2") (pinfunction "2_2") (pintype "passive"))
    )
    (net (code "61") (name "Net-(C122-Pad1)") (class "Default")
      (node (ref "C122") (pin "1") (pinfunction "1_1") (pintype "passive"))
      (node (ref "R123") (pin "2") (pinfunction "2_2") (pintype "passive"))
    )
    (net (code "62") (name "Net-(IC2-VDD)") (class "Default")
      (node (ref "C2") (pin "2") (pinfunction "2_2") (pintype "passive"))
      (node (ref "IC2") (pin "1") (pinfunction "VDD_1") (pintype "power_in"))
      (node (ref "R3") (pin "2") (pinfunction "2_2") (pintype "passive"))
    )
    (net (code "63") (name "Net-(IC3-OUT)") (class "Default")
      (node (ref "IC3") (pin "6") (pinfunction "OUT_6") (pintype "output"))
      (node (ref "R144") (pin "2") (pinfunction "2_2") (pintype "passive"))
    )
    (net (code "64") (name "Net-(IC3-VCC)") (class "Default")
      (node (ref "C3") (pin "2") (pinfunction "2_2") (pintype "passive"))
      (node (ref "IC3") (pin "1") (pinfunction "VCC_1") (pintype "power_in"))
      (node (ref "R6") (pin "1") (pinfunction "1_1") (pintype "passive"))
    )
    (net (code "65") (name "Net-(IC5-VDD)") (class "Default")
      (node (ref "C5") (pin "2") (pinfunction "2_2") (pintype "passive"))
      (node (ref "IC5") (pin "1") (pinfunction "VDD_1") (pintype "power_in"))
      (node (ref "R9") (pin "1") (pinfunction "1_1") (pintype "passive"))
    )
    (net (code "66") (name "Net-(IC9-OUT)") (class "Default")
      (node (ref "IC9") (pin "6") (pinfunction "OUT_6") (pintype "output"))
      (node (ref "R145") (pin "2") (pinfunction "2_2") (pintype "passive"))
    )
    (net (code "67") (name "Net-(IC9-VCC)") (class "Default")
      (node (ref "C99") (pin "2") (pinfunction "2_2") (pintype "passive"))
      (node (ref "IC9") (pin "1") (pinfunction "VCC_1") (pintype "power_in"))
      (node (ref "R160") (pin "1") (pinfunction "1_1") (pintype "passive"))
    )
    (net (code "68") (name "Net-(IC30-VCC)") (class "Default")
      (node (ref "C8") (pin "2") (pinfunction "2_2") (pintype "passive"))
      (node (ref "IC30") (pin "8") (pinfunction "VCC_8") (pintype "power_in"))
      (node (ref "IC8") (pin "4") (pinfunction "VCC_4") (pintype "power_in"))
      (node (ref "R14") (pin "2") (pinfunction "2_2") (pintype "passive"))
    )
    (net (code "69") (name "P3V3s") (class "Default")
      (node (ref "C9") (pin "2") (pinfunction "2_2") (pintype "passive"))
      (node (ref "D1") (pin "4") (pinfunction "VCC_4") (pintype "power_in"))
      (node (ref "J10") (pin "34") (pinfunction "34_34") (pintype "bidirectional"))
      (node (ref "R133") (pin "1") (pinfunction "1_1") (pintype "passive"))
      (node (ref "R134") (pin "1") (pinfunction "1_1") (pintype "passive"))
      (node (ref "R14") (pin "1") (pinfunction "1_1") (pintype "passive"))
      (node (ref "R141") (pin "1") (pinfunction "1_1") (pintype "passive"))
      (node (ref "R142") (pin "1") (pinfunction "1_1") (pintype "passive"))
      (node (ref "R160") (pin "2") (pinfunction "2_2") (pintype "passive"))
      (node (ref "R3") (pin "1") (pinfunction "1_1") (pintype "passive"))
      (node (ref "R6") (pin "2") (pinfunction "2_2") (pintype "passive"))
      (node (ref "R9") (pin "2") (pinfunction "2_2") (pintype "passive"))
      (node (ref "TP12") (pin "1") (pinfunction "1_1") (pintype "bidirectional"))
    )
    (net (code "70") (name "P12V0") (class "Default")
      (node (ref "J10") (pin "31") (pinfunction "31_31") (pintype "bidirectional"))
      (node (ref "J10") (pin "32") (pinfunction "32_32") (pintype "bidirectional"))
      (node (ref "J10") (pin "33") (pinfunction "33_33") (pintype "bidirectional"))
      (node (ref "TP13") (pin "1") (pinfunction "1_1") (pintype "bidirectional"))
    )
    (net (code "71") (name "P12V0AS") (class "Default")
      (node (ref "J6") (pin "15") (pinfunction "15_15") (pintype "bidirectional"))
    )
    (net (code "72") (name "unconnected-(IC8-NC-Pad5)") (class "Default")
      (node (ref "IC8") (pin "5") (pinfunction "NC_5") (pintype "passive"))
    )
    (net (code "73") (name "unconnected-(IC30-A0_(NC)-Pad1)") (class "Default")
      (node (ref "IC30") (pin "1") (pinfunction "A0_(NC)_1") (pintype "input+no_connect"))
    )
    (net (code "74") (name "unconnected-(IC30-A1_(NC)-Pad2)") (class "Default")
      (node (ref "IC30") (pin "2") (pinfunction "A1_(NC)_2") (pintype "input+no_connect"))
    )
    (net (code "75") (name "unconnected-(IC30-A2_(NC)-Pad3)") (class "Default")
      (node (ref "IC30") (pin "3") (pinfunction "A2_(NC)_3") (pintype "input+no_connect"))
    )
    (net (code "76") (name "unconnected-(IC30-NC-Pad7)") (class "Default")
      (node (ref "IC30") (pin "7") (pinfunction "NC_7") (pintype "passive"))
    )
    (net (code "77") (name "unconnected-(J1-Pad25)") (class "Default")
      (node (ref "J1") (pin "25") (pinfunction "25_25") (pintype "bidirectional"))
    )
    (net (code "78") (name "unconnected-(J1-Pad26)") (class "Default")
      (node (ref "J1") (pin "26") (pinfunction "26_26") (pintype "bidirectional"))
    )
    (net (code "79") (name "unconnected-(J6-Pad14)") (class "Default")
      (node (ref "J6") (pin "14") (pinfunction "14_14") (pintype "bidirectional"))
    )
  )
)
